# Connectors.net
KiCad netlist of a schematic drawn in Altium Designer
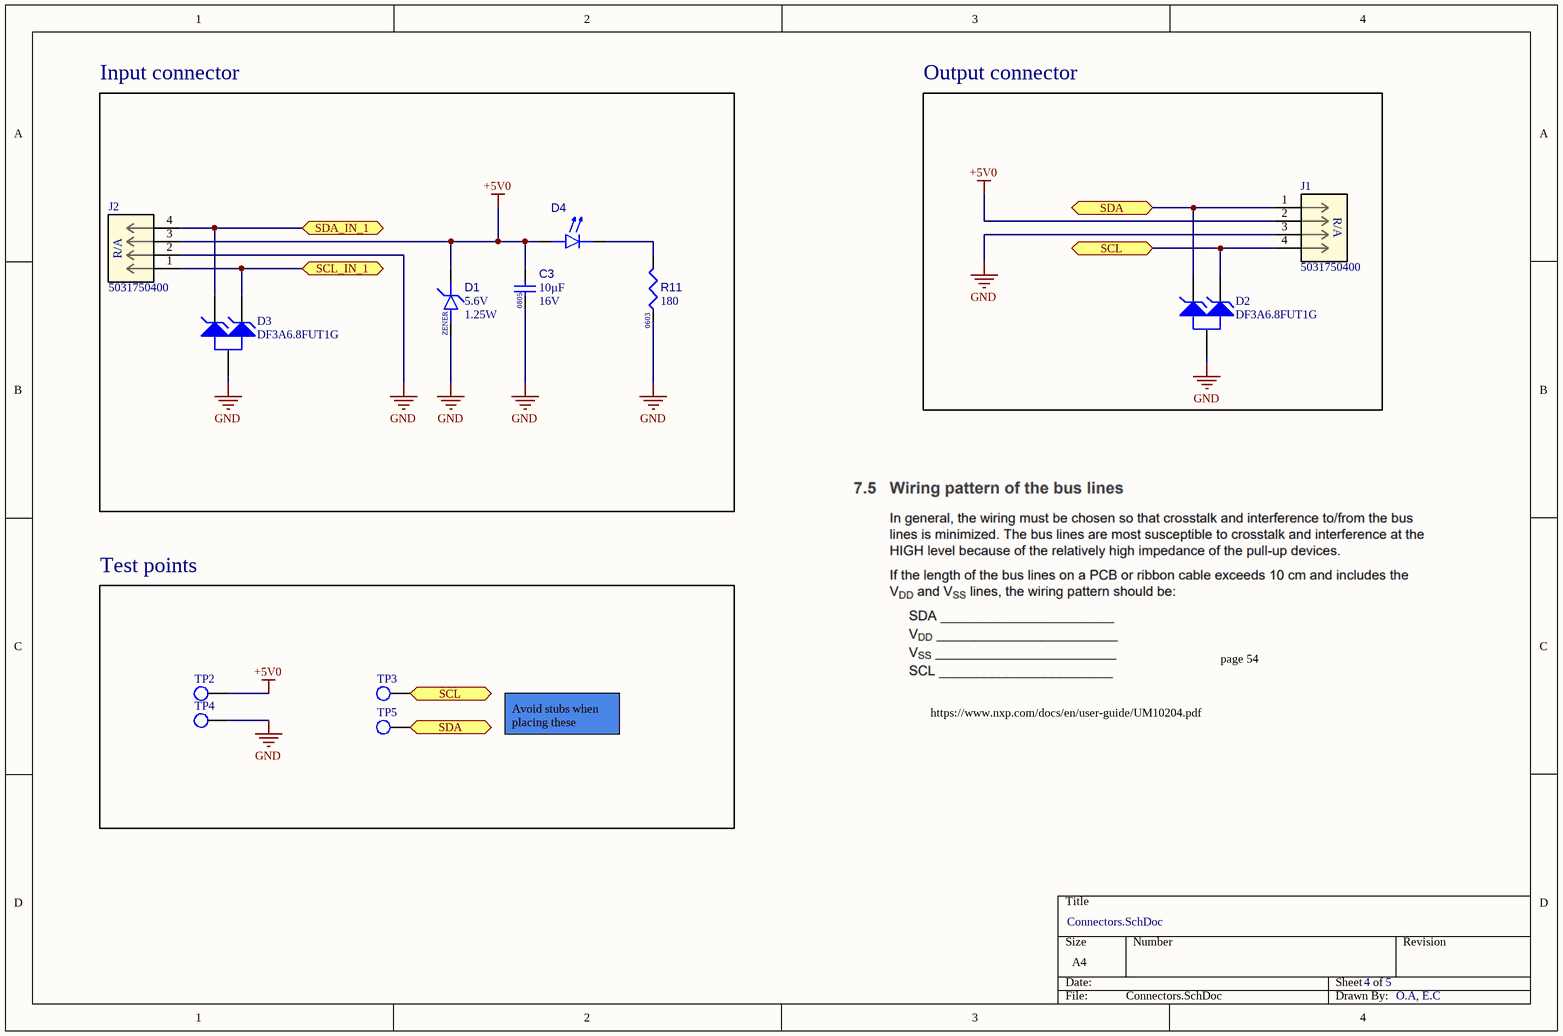
[diagram p0: Connectors.SchDoc]

(export (version "E")
  (design (tool "Eeschema 10.0.6"))
  (components
    (comp (ref "C3")
      (value "10µF")
      (footprint "CAP CER 10UF 16V X5R 0805-Footprint-1")
      (fields
        (field (name "VOLTAGE RATING") "16V")
        (field (name "CASE/PACKAGE") "0805")
        (field (name "Comment") "CAP CER 10UF 16V X5R 0805")
      )
      (libsource (lib "hawaiirobotics") (part "CAP-NP-2"))
    )
    (comp (ref "D1")
      (value "BZG05C5V6-M3-08")
      (footprint "FP-S8-V-3848_01-003-MFG")
      (description "Zener Diode, 5.6V V(Z), 7.14%, 1.25W, Silicon, Unidirectional, DO-214AC")
      (fields
        (field (name "DIODE TYPE") "ZENER")
        (field (name "REFERENCE VOLTAGE-NOM") "5.6V")
        (field (name "MAX POWER DISSIPATION") "1.25W")
      )
      (libsource (lib "hawaiirobotics") (part "DIODE-2"))
    )
    (comp (ref "D2")
      (value "DF3A6.8FUT1G")
      (footprint "ONSC-SC-70-3-419-04_V")
      (description "Trans Voltage Suppressor Diode, 150W, Unidirectional, 2 Element, Silicon")
      (libsource (lib "hawaiirobotics") (part "ONSC-K1K2A3-3"))
    )
    (comp (ref "D3")
      (value "DF3A6.8FUT1G")
      (footprint "ONSC-SC-70-3-419-04_V")
      (description "Trans Voltage Suppressor Diode, 150W, Unidirectional, 2 Element, Silicon")
      (libsource (lib "hawaiirobotics") (part "ONSC-K1K2A3-3"))
    )
    (comp (ref "D4")
      (value "150060RS75000")
      (footprint "WL-SMCW_0603_150060xx75000")
      (description "Single Color LED, Red, Water Clear, 1.1mm")
      (libsource (lib "hawaiirobotics") (part "DIODE-LED-2"))
    )
    (comp (ref "J1")
      (value "5031750400")
      (footprint "5031750400-Footprint-1")
      (libsource (lib "hawaiirobotics") (part "5031750400-Symbol-1"))
    )
    (comp (ref "J2")
      (value "5031750400")
      (footprint "5031750400-Footprint-1")
      (libsource (lib "") (part "5031750400-Symbol-1_1"))
    )
    (comp (ref "R11")
      (value "180")
      (footprint "RESC0603(1608)_N")
      (fields
        (field (name "TOLERANCE") "5%")
        (field (name "CASE/PACKAGE") "0603")
        (field (name "POWER") "100mW")
        (field (name "Comment") "RC0603JR-07180RL")
      )
      (libsource (lib "hawaiirobotics") (part "RES-2"))
    )
    (comp (ref "TP2")
      (value "RCUCTE")
      (footprint "FP-S2761-46R-MFG")
      (description "Test point")
      (libsource (lib "hawaiirobotics") (part "RCUCTE-Symbol-1"))
    )
    (comp (ref "TP3")
      (value "RCUCTE")
      (footprint "FP-S2761-46R-MFG")
      (description "Test point")
      (libsource (lib "hawaiirobotics") (part "RCUCTE-Symbol-1"))
    )
    (comp (ref "TP4")
      (value "RCUCTE")
      (footprint "FP-S2761-46R-MFG")
      (description "Test point")
      (libsource (lib "hawaiirobotics") (part "RCUCTE-Symbol-1"))
    )
    (comp (ref "TP5")
      (value "RCUCTE")
      (footprint "FP-S2761-46R-MFG")
      (description "Test point")
      (libsource (lib "hawaiirobotics") (part "RCUCTE-Symbol-1"))
    )
  )
  (nets
    (net (code "1") (name "+5V0") (class "Default")
      (node (ref "C3") (pin "2") (pinfunction "2_2") (pintype "passive"))
      (node (ref "D1") (pin "1") (pinfunction "K_1") (pintype "passive"))
      (node (ref "D4") (pin "2") (pinfunction "A_2") (pintype "passive"))
      (node (ref "J1") (pin "2") (pinfunction "2_2") (pintype "passive"))
      (node (ref "J2") (pin "3") (pinfunction "3_3") (pintype "passive"))
      (node (ref "TP2") (pin "1") (pinfunction "1_1") (pintype "passive"))
    )
    (net (code "2") (name "/SCL") (class "Default")
      (node (ref "D2") (pin "2") (pinfunction "K2_2") (pintype "passive"))
      (node (ref "J1") (pin "4") (pinfunction "4_4") (pintype "passive"))
      (node (ref "TP3") (pin "1") (pinfunction "1_1") (pintype "passive"))
    )
    (net (code "3") (name "/SCL_IN_1") (class "Default")
      (node (ref "D3") (pin "2") (pinfunction "K2_2") (pintype "passive"))
      (node (ref "J2") (pin "1") (pinfunction "1_1") (pintype "passive"))
    )
    (net (code "4") (name "/SDA") (class "Default")
      (node (ref "D2") (pin "1") (pinfunction "K1_1") (pintype "passive"))
      (node (ref "J1") (pin "1") (pinfunction "1_1") (pintype "passive"))
      (node (ref "TP5") (pin "1") (pinfunction "1_1") (pintype "passive"))
    )
    (net (code "5") (name "/SDA_IN_1") (class "Default")
      (node (ref "D3") (pin "1") (pinfunction "K1_1") (pintype "passive"))
      (node (ref "J2") (pin "4") (pinfunction "4_4") (pintype "passive"))
    )
    (net (code "6") (name "GND") (class "Default")
      (node (ref "C3") (pin "1") (pinfunction "1_1") (pintype "passive"))
      (node (ref "D1") (pin "2") (pinfunction "A_2") (pintype "passive"))
      (node (ref "D2") (pin "3") (pinfunction "A_3") (pintype "passive"))
      (node (ref "D3") (pin "3") (pinfunction "A_3") (pintype "passive"))
      (node (ref "J1") (pin "3") (pinfunction "3_3") (pintype "passive"))
      (node (ref "J2") (pin "2") (pinfunction "2_2") (pintype "passive"))
      (node (ref "R11") (pin "1") (pinfunction "1_1") (pintype "passive"))
      (node (ref "TP4") (pin "1") (pinfunction "1_1") (pintype "passive"))
    )
    (net (code "7") (name "Net-(D4-K)") (class "Default")
      (node (ref "D4") (pin "1") (pinfunction "K_1") (pintype "passive"))
      (node (ref "R11") (pin "2") (pinfunction "2_2") (pintype "passive"))
    )
  )
)
